# Connectors.net
KiCad netlist of a schematic drawn in Altium Designer
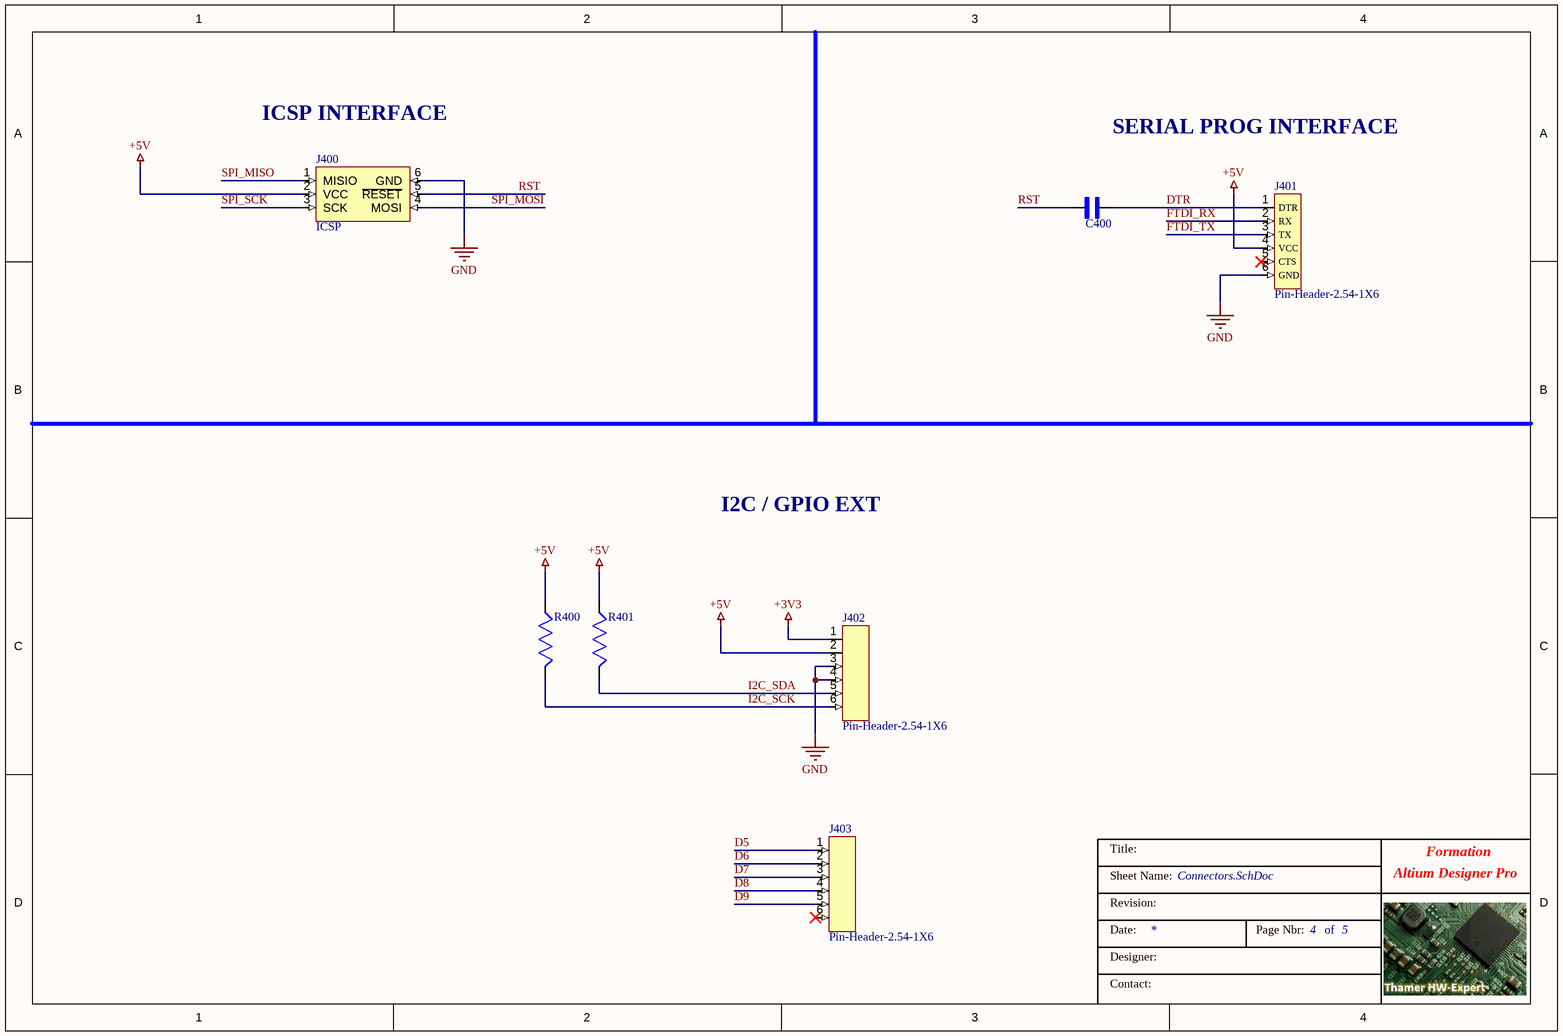
[diagram p0: Connectors.SchDoc]

(export (version "E")
  (design (tool "Eeschema 10.0.6"))
  (components
    (comp (ref "C400")
      (value "GCM21BR71H104KA37K")
      (footprint "CAPC2012X135N")
      (description ".1UF 50V 10% 080")
      (fields (field (name "MF") "{'manufacturer': u'Murata'}"))
      (libsource (lib "Capacitor") (part "GCM21BR71H104KA37K"))
    )
    (comp (ref "J400")
      (value "ICSP")
      (footprint "PINHEADER-3X2_2.54MM")
      (libsource (lib "sch_Library") (part "ICSP"))
    )
    (comp (ref "J401")
      (value "Pin-Header-2.54-1X6")
      (footprint "PIN-HEADER-2.54MM-1X6")
      (libsource (lib "") (part "Pin-Header-2.54-1X6_1"))
    )
    (comp (ref "J402")
      (value "Pin-Header-2.54-1X6")
      (footprint "PIN-HEADER-2.54MM-1X6")
      (libsource (lib "sch_Library") (part "Pin-Header-2.54-1X6"))
    )
    (comp (ref "J403")
      (value "Pin-Header-2.54-1X6")
      (footprint "PIN-HEADER-2.54MM-1X6")
      (libsource (lib "sch_Library") (part "Pin-Header-2.54-1X6"))
    )
    (comp (ref "R400")
      (value "RC0805JR-134K7L")
      (footprint "RESC2012X60N")
      (fields (field (name "MF") "{'manufacturer': u'Yageo'}"))
      (libsource (lib "Resistor") (part "RC0805JR-134K7L"))
    )
    (comp (ref "R401")
      (value "RC0805JR-134K7L")
      (footprint "RESC2012X60N")
      (fields (field (name "MF") "{'manufacturer': u'Yageo'}"))
      (libsource (lib "Resistor") (part "RC0805JR-134K7L"))
    )
  )
  (nets
    (net (code "1") (name "+3V3") (class "Default") (node (ref "J402") (pin "1") (pintype "input")))
    (net (code "2") (name "+5V") (class "Default")
      (node (ref "J400") (pin "2") (pinfunction "VCC_2") (pintype "input"))
      (node (ref "J401") (pin "4") (pinfunction "VCC_4") (pintype "input"))
      (node (ref "J402") (pin "2") (pintype "input"))
      (node (ref "R400") (pin "2") (pinfunction "2_2") (pintype "passive"))
      (node (ref "R401") (pin "2") (pinfunction "2_2") (pintype "passive"))
    )
    (net (code "3") (name "/D5") (class "Default") (node (ref "J403") (pin "1") (pintype "input")))
    (net (code "4") (name "/D6") (class "Default") (node (ref "J403") (pin "2") (pintype "input")))
    (net (code "5") (name "/D7") (class "Default") (node (ref "J403") (pin "3") (pintype "input")))
    (net (code "6") (name "/D8") (class "Default") (node (ref "J403") (pin "4") (pintype "input")))
    (net (code "7") (name "/D9") (class "Default") (node (ref "J403") (pin "5") (pintype "input")))
    (net (code "8") (name "/DTR") (class "Default")
      (node (ref "C400") (pin "2") (pinfunction "2_2") (pintype "passive"))
      (node (ref "J401") (pin "1") (pinfunction "DTR_1") (pintype "passive"))
    )
    (net (code "9") (name "/FTDI_RX") (class "Default")
      (node (ref "J401") (pin "2") (pinfunction "RX_2") (pintype "input"))
    )
    (net (code "10") (name "/FTDI_TX") (class "Default")
      (node (ref "J401") (pin "3") (pinfunction "TX_3") (pintype "input"))
    )
    (net (code "11") (name "/I2C_SCK") (class "Default")
      (node (ref "J402") (pin "6") (pintype "input"))
      (node (ref "R400") (pin "1") (pinfunction "1_1") (pintype "passive"))
    )
    (net (code "12") (name "/I2C_SDA") (class "Default")
      (node (ref "J402") (pin "5") (pintype "input"))
      (node (ref "R401") (pin "1") (pinfunction "1_1") (pintype "passive"))
    )
    (net (code "13") (name "/RST") (class "Default")
      (node (ref "C400") (pin "1") (pinfunction "1_1") (pintype "passive"))
      (node (ref "J400") (pin "5") (pinfunction "~{RESET}_5") (pintype "input"))
    )
    (net (code "14") (name "/SPI_MISO") (class "Default")
      (node (ref "J400") (pin "1") (pinfunction "MISIO_1") (pintype "input"))
    )
    (net (code "15") (name "/SPI_MOSI") (class "Default")
      (node (ref "J400") (pin "4") (pinfunction "MOSI_4") (pintype "input"))
    )
    (net (code "16") (name "/SPI_SCK") (class "Default")
      (node (ref "J400") (pin "3") (pinfunction "SCK_3") (pintype "input"))
    )
    (net (code "17") (name "GND") (class "Default")
      (node (ref "J400") (pin "6") (pinfunction "GND_6") (pintype "input"))
      (node (ref "J401") (pin "6") (pinfunction "GND_6") (pintype "input"))
      (node (ref "J402") (pin "3") (pintype "input"))
      (node (ref "J402") (pin "4") (pintype "input"))
    )
    (net (code "18") (name "unconnected-(J401-CTS-Pad5)") (class "Default")
      (node (ref "J401") (pin "5") (pinfunction "CTS_5") (pintype "input+no_connect"))
    )
    (net (code "19") (name "unconnected-(J403-Pad6)") (class "Default")
      (node (ref "J403") (pin "6") (pintype "input+no_connect"))
    )
  )
)
